# rxv1.net
KiCad netlist of a schematic drawn in Altium Designer
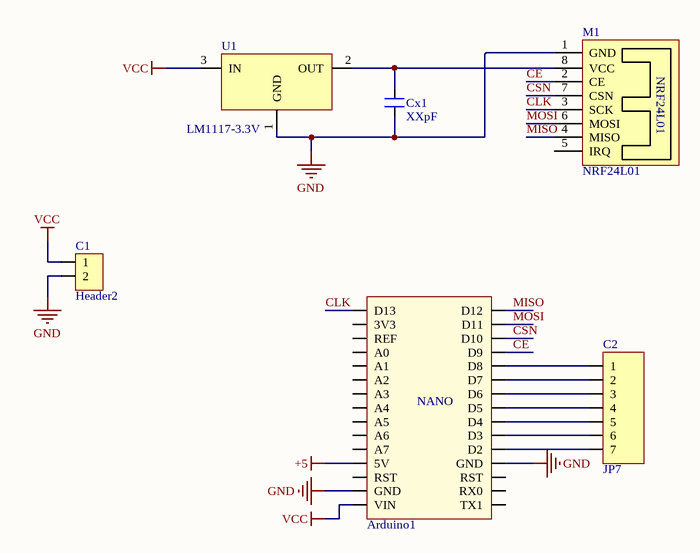
[diagram p0: rxv1.SchDoc]

(export (version "E")
  (design (tool "Eeschema 10.0.6"))
  (components
    (comp (ref "Arduino1")
      (value "Arduino Nano")
      (footprint "Arduino Nano")
      (description "Arduino NANO")
      (libsource (lib "LIBRARY") (part "Arduino Nano"))
    )
    (comp (ref "C1")
      (value "Header2")
      (footprint "Header2")
      (description "Header IDC, 2 x 1 Pin Vertical 2.54mm Pitch (Non-Boxed, Male)")
      (fields
        (field (name "MANUFACTURER") "Würth Elektronik eiSos GmbH")
        (field (name "PARTNO") "613002143121")
        (field (name "CREATED BY") "Karrer Zheng")
      )
      (libsource (lib "LIBRARY") (part "Header2"))
    )
    (comp (ref "C2")
      (value "JP7")
      (footprint "JP7-C1T")
      (description "WR-PHD 2.54 mm Angled Socket Header")
      (fields
        (field (name "MANUFACTURER") "Würth Elektronik eiSos GmbH")
        (field (name "PARTNO") "613007143121")
        (field (name "CREATED BY") "Karrer Zheng")
      )
      (libsource (lib "LIBRARY") (part "JP7"))
    )
    (comp (ref "Cx1") (value "XXpF") (footprint "CN-SMD-1206") (libsource (lib "LIBRARY") (part "CN")))
    (comp (ref "M1") (value "NRF24L01") (footprint "NRF24L01") (libsource (lib "LIBRARY") (part "NRF24L01")))
    (comp (ref "U1")
      (value "LM1117-3.3V")
      (footprint "SOT223")
      (description "800mA Low-Dropout Linear Regulator")
      (fields (field (name "CREATOR") "Nguyen Ba Bien"))
      (libsource (lib "LIBRARY") (part "LM1117"))
    )
  )
  (nets
    (net (code "1") (name "+5") (class "Default")
      (node (ref "Arduino1") (pin "5V") (pinfunction "5V_5V") (pintype "passive"))
    )
    (net (code "2") (name "/CE") (class "Default")
      (node (ref "Arduino1") (pin "D9") (pinfunction "D9_D9") (pintype "passive"))
      (node (ref "M1") (pin "2") (pinfunction "CE_2") (pintype "passive"))
    )
    (net (code "3") (name "/CLK") (class "Default")
      (node (ref "Arduino1") (pin "D13") (pinfunction "D13_D13") (pintype "passive"))
      (node (ref "M1") (pin "3") (pinfunction "SCK_3") (pintype "passive"))
    )
    (net (code "4") (name "/CSN") (class "Default")
      (node (ref "Arduino1") (pin "D10") (pinfunction "D10_D10") (pintype "passive"))
      (node (ref "M1") (pin "7") (pinfunction "CSN_7") (pintype "passive"))
    )
    (net (code "5") (name "/MISO") (class "Default")
      (node (ref "Arduino1") (pin "D12") (pinfunction "D12_D12") (pintype "passive"))
      (node (ref "M1") (pin "4") (pinfunction "MISO_4") (pintype "passive"))
    )
    (net (code "6") (name "/MOSI") (class "Default")
      (node (ref "Arduino1") (pin "D11") (pinfunction "D11_D11") (pintype "passive"))
      (node (ref "M1") (pin "6") (pinfunction "MOSI_6") (pintype "passive"))
    )
    (net (code "7") (name "GND") (class "Default")
      (node (ref "Arduino1") (pin "GND") (pinfunction "GND_GND") (pintype "passive"))
      (node (ref "C1") (pin "2") (pinfunction "2_2") (pintype "passive"))
      (node (ref "Cx1") (pin "1") (pinfunction "1_1") (pintype "passive"))
      (node (ref "M1") (pin "1") (pinfunction "GND_1") (pintype "passive"))
      (node (ref "U1") (pin "1") (pinfunction "GND_1") (pintype "passive"))
    )
    (net (code "8") (name "Net-(Arduino1-PadD2)") (class "Default")
      (node (ref "Arduino1") (pin "D2") (pinfunction "D2_D2") (pintype "passive"))
      (node (ref "C2") (pin "7") (pinfunction "7_7") (pintype "passive"))
    )
    (net (code "9") (name "Net-(Arduino1-PadD3)") (class "Default")
      (node (ref "Arduino1") (pin "D3") (pinfunction "D3_D3") (pintype "passive"))
      (node (ref "C2") (pin "6") (pinfunction "6_6") (pintype "passive"))
    )
    (net (code "10") (name "Net-(Arduino1-PadD4)") (class "Default")
      (node (ref "Arduino1") (pin "D4") (pinfunction "D4_D4") (pintype "passive"))
      (node (ref "C2") (pin "5") (pinfunction "5_5") (pintype "passive"))
    )
    (net (code "11") (name "Net-(Arduino1-PadD5)") (class "Default")
      (node (ref "Arduino1") (pin "D5") (pinfunction "D5_D5") (pintype "passive"))
      (node (ref "C2") (pin "4") (pinfunction "4_4") (pintype "passive"))
    )
    (net (code "12") (name "Net-(Arduino1-PadD6)") (class "Default")
      (node (ref "Arduino1") (pin "D6") (pinfunction "D6_D6") (pintype "passive"))
      (node (ref "C2") (pin "3") (pinfunction "3_3") (pintype "passive"))
    )
    (net (code "13") (name "Net-(Arduino1-PadD7)") (class "Default")
      (node (ref "Arduino1") (pin "D7") (pinfunction "D7_D7") (pintype "passive"))
      (node (ref "C2") (pin "2") (pinfunction "2_2") (pintype "passive"))
    )
    (net (code "14") (name "Net-(Arduino1-PadD8)") (class "Default")
      (node (ref "Arduino1") (pin "D8") (pinfunction "D8_D8") (pintype "passive"))
      (node (ref "C2") (pin "1") (pinfunction "1_1") (pintype "passive"))
    )
    (net (code "15") (name "Net-(M1-VCC)") (class "Default")
      (node (ref "Cx1") (pin "2") (pinfunction "2_2") (pintype "passive"))
      (node (ref "M1") (pin "8") (pinfunction "VCC_8") (pintype "passive"))
      (node (ref "U1") (pin "2") (pinfunction "OUT_2") (pintype "passive"))
    )
    (net (code "16") (name "VCC") (class "Default")
      (node (ref "Arduino1") (pin "VIN") (pinfunction "VIN_VIN") (pintype "passive"))
      (node (ref "C1") (pin "1") (pinfunction "1_1") (pintype "passive"))
      (node (ref "U1") (pin "3") (pinfunction "IN_3") (pintype "passive"))
    )
    (net (code "17") (name "unconnected-(Arduino1-Pad3V3)") (class "Default")
      (node (ref "Arduino1") (pin "3V3") (pinfunction "3V3_3V3") (pintype "passive"))
    )
    (net (code "18") (name "unconnected-(Arduino1-PadA0)") (class "Default")
      (node (ref "Arduino1") (pin "A0") (pinfunction "A0_A0") (pintype "passive"))
    )
    (net (code "19") (name "unconnected-(Arduino1-PadA1)") (class "Default")
      (node (ref "Arduino1") (pin "A1") (pinfunction "A1_A1") (pintype "passive"))
    )
    (net (code "20") (name "unconnected-(Arduino1-PadA2)") (class "Default")
      (node (ref "Arduino1") (pin "A2") (pinfunction "A2_A2") (pintype "passive"))
    )
    (net (code "21") (name "unconnected-(Arduino1-PadA3)") (class "Default")
      (node (ref "Arduino1") (pin "A3") (pinfunction "A3_A3") (pintype "passive"))
    )
    (net (code "22") (name "unconnected-(Arduino1-PadA4)") (class "Default")
      (node (ref "Arduino1") (pin "A4") (pinfunction "A4_A4") (pintype "passive"))
    )
    (net (code "23") (name "unconnected-(Arduino1-PadA5)") (class "Default")
      (node (ref "Arduino1") (pin "A5") (pinfunction "A5_A5") (pintype "passive"))
    )
    (net (code "24") (name "unconnected-(Arduino1-PadA6)") (class "Default")
      (node (ref "Arduino1") (pin "A6") (pinfunction "A6_A6") (pintype "passive"))
    )
    (net (code "25") (name "unconnected-(Arduino1-PadA7)") (class "Default")
      (node (ref "Arduino1") (pin "A7") (pinfunction "A7_A7") (pintype "passive"))
    )
    (net (code "26") (name "unconnected-(Arduino1-PadREF)") (class "Default")
      (node (ref "Arduino1") (pin "REF") (pinfunction "REF_REF") (pintype "passive"))
    )
    (net (code "27") (name "unconnected-(Arduino1-PadRST)") (class "Default")
      (node (ref "Arduino1") (pin "RST") (pinfunction "RST_RST") (pintype "passive"))
    )
    (net (code "28") (name "unconnected-(Arduino1-PadRST)_1") (class "Default")
      (node (ref "Arduino1") (pin "RST") (pinfunction "RST_RST") (pintype "passive"))
    )
    (net (code "29") (name "unconnected-(Arduino1-PadRX0)") (class "Default")
      (node (ref "Arduino1") (pin "RX0") (pinfunction "RX0_RX0") (pintype "passive"))
    )
    (net (code "30") (name "unconnected-(Arduino1-PadTX1)") (class "Default")
      (node (ref "Arduino1") (pin "TX1") (pinfunction "TX1_TX1") (pintype "passive"))
    )
    (net (code "31") (name "unconnected-(M1-IRQ-Pad5)") (class "Default")
      (node (ref "M1") (pin "5") (pinfunction "IRQ_5") (pintype "passive"))
    )
  )
)
